# electronic_piano.net
KiCad netlist of a schematic drawn in EAGLE
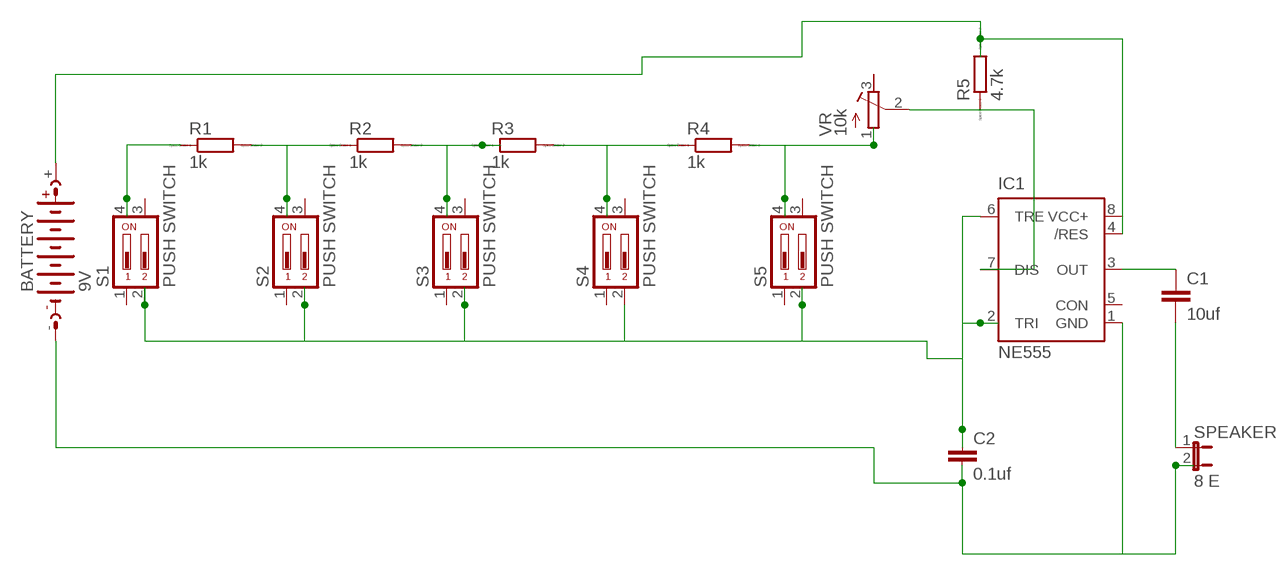
[diagram p0: schematic, sheet 1]

(export (version "E")
  (design (tool "Eeschema 10.0.6"))
  (components
    (comp (ref "BATTERY")
      (value "9V")
      (footprint "eagle-import:AB9V")
      (libsource (lib "eagle-import") (part "AB9V"))
    )
    (comp (ref "C1")
      (value "10uf")
      (footprint "eagle-import:C5B7.2")
      (libsource (lib "eagle-import") (part "C5/7.2"))
    )
    (comp (ref "C2")
      (value "0.1uf")
      (footprint "eagle-import:C2.5-2")
      (libsource (lib "eagle-import") (part "C2.5/2"))
    )
    (comp (ref "IC1")
      (value "NE555")
      (footprint "eagle-import:DIL-08")
      (fields (field (name "MF") "Arrow Electronics") (field (name "MPN") "NE555N"))
      (libsource (lib "eagle-import") (part "NE555"))
    )
    (comp (ref "R1")
      (value "1k")
      (footprint "eagle-import:0204_7")
      (libsource (lib "eagle-import") (part "R0204/7"))
    )
    (comp (ref "R2")
      (value "1k")
      (footprint "eagle-import:0204_7")
      (libsource (lib "eagle-import") (part "R0204/7"))
    )
    (comp (ref "R3")
      (value "1k")
      (footprint "eagle-import:0204_7")
      (libsource (lib "eagle-import") (part "R0204/7"))
    )
    (comp (ref "R4")
      (value "1k")
      (footprint "eagle-import:0204_7")
      (libsource (lib "eagle-import") (part "R0204/7"))
    )
    (comp (ref "R5")
      (value "4.7k")
      (footprint "eagle-import:0204_7")
      (libsource (lib "eagle-import") (part "R0204/7"))
    )
    (comp (ref "S1")
      (value "PUSH SWITCH")
      (footprint "eagle-import:DS-02")
      (libsource (lib "eagle-import") (part "DS02"))
    )
    (comp (ref "S2")
      (value "PUSH SWITCH")
      (footprint "eagle-import:DS-02")
      (libsource (lib "eagle-import") (part "DS02"))
    )
    (comp (ref "S3")
      (value "PUSH SWITCH")
      (footprint "eagle-import:DS-02")
      (libsource (lib "eagle-import") (part "DS02"))
    )
    (comp (ref "S4")
      (value "PUSH SWITCH")
      (footprint "eagle-import:DS-02")
      (libsource (lib "eagle-import") (part "DS02"))
    )
    (comp (ref "S5")
      (value "PUSH SWITCH")
      (footprint "eagle-import:DS-02")
      (libsource (lib "eagle-import") (part "DS02"))
    )
    (comp (ref "SPEAKER")
      (value "8 E")
      (footprint "eagle-import:JP1")
      (libsource (lib "eagle-import") (part "JP1E"))
    )
    (comp (ref "VR")
      (value "10k")
      (footprint "eagle-import:RTRIM64P")
      (libsource (lib "eagle-import") (part "R-TRIMM64P"))
    )
  )
  (nets
    (net (code "1") (name "Net-(C1-Pad2)") (class "Default")
      (node (ref "C1") (pin "2") (pinfunction "2_2") (pintype "passive"))
      (node (ref "SPEAKER") (pin "1") (pinfunction "1_1") (pintype "passive"))
    )
    (net (code "2") (name "Net-(IC1-DIS)") (class "Default")
      (node (ref "IC1") (pin "7") (pinfunction "DIS_7") (pintype "input"))
      (node (ref "R5") (pin "1") (pinfunction "1_1") (pintype "passive"))
      (node (ref "VR") (pin "2") (pinfunction "S_2") (pintype "passive"))
    )
    (net (code "3") (name "Net-(IC1-GND)") (class "Default")
      (node (ref "BATTERY") (pin "-") (pinfunction "-_-") (pintype "passive"))
      (node (ref "C2") (pin "2") (pinfunction "2_2") (pintype "passive"))
      (node (ref "IC1") (pin "1") (pinfunction "GND_1") (pintype "power_in"))
      (node (ref "SPEAKER") (pin "2") (pinfunction "2_2") (pintype "passive"))
    )
    (net (code "4") (name "Net-(IC1-OUT)") (class "Default")
      (node (ref "C1") (pin "1") (pinfunction "1_1") (pintype "passive"))
      (node (ref "IC1") (pin "3") (pinfunction "OUT_3") (pintype "output"))
    )
    (net (code "5") (name "Net-(IC1-TRE)") (class "Default")
      (node (ref "C2") (pin "1") (pinfunction "1_1") (pintype "passive"))
      (node (ref "IC1") (pin "2") (pinfunction "TRI_2") (pintype "input"))
      (node (ref "IC1") (pin "6") (pinfunction "TRE_6") (pintype "input"))
      (node (ref "S1") (pin "2") (pinfunction "2_2") (pintype "passive"))
      (node (ref "S2") (pin "2") (pinfunction "2_2") (pintype "passive"))
      (node (ref "S3") (pin "2") (pinfunction "2_2") (pintype "passive"))
      (node (ref "S4") (pin "2") (pinfunction "2_2") (pintype "passive"))
      (node (ref "S5") (pin "2") (pinfunction "2_2") (pintype "passive"))
    )
    (net (code "6") (name "Net-(IC1-VCC+)") (class "Default")
      (node (ref "BATTERY") (pin "+") (pinfunction "+_+") (pintype "passive"))
      (node (ref "IC1") (pin "4") (pinfunction "/RES_4") (pintype "input"))
      (node (ref "IC1") (pin "8") (pinfunction "VCC+_8") (pintype "power_in"))
      (node (ref "R5") (pin "2") (pinfunction "2_2") (pintype "passive"))
    )
    (net (code "7") (name "Net-(R1-Pad1)") (class "Default")
      (node (ref "R1") (pin "1") (pinfunction "1_1") (pintype "passive"))
      (node (ref "S1") (pin "4") (pinfunction "4_4") (pintype "passive"))
    )
    (net (code "8") (name "Net-(R1-Pad2)") (class "Default")
      (node (ref "R1") (pin "2") (pinfunction "2_2") (pintype "passive"))
      (node (ref "R2") (pin "1") (pinfunction "1_1") (pintype "passive"))
      (node (ref "S2") (pin "4") (pinfunction "4_4") (pintype "passive"))
    )
    (net (code "9") (name "Net-(R2-Pad2)") (class "Default")
      (node (ref "R2") (pin "2") (pinfunction "2_2") (pintype "passive"))
      (node (ref "R3") (pin "1") (pinfunction "1_1") (pintype "passive"))
      (node (ref "S3") (pin "4") (pinfunction "4_4") (pintype "passive"))
    )
    (net (code "10") (name "Net-(R3-Pad2)") (class "Default")
      (node (ref "R3") (pin "2") (pinfunction "2_2") (pintype "passive"))
      (node (ref "R4") (pin "1") (pinfunction "1_1") (pintype "passive"))
      (node (ref "S4") (pin "4") (pinfunction "4_4") (pintype "passive"))
    )
    (net (code "11") (name "Net-(VR-E)") (class "Default")
      (node (ref "R4") (pin "2") (pinfunction "2_2") (pintype "passive"))
      (node (ref "S5") (pin "4") (pinfunction "4_4") (pintype "passive"))
      (node (ref "VR") (pin "1") (pinfunction "E_1") (pintype "passive"))
    )
    (net (code "12") (name "unconnected-(IC1-CON-Pad5)") (class "Default")
      (node (ref "IC1") (pin "5") (pinfunction "CON_5") (pintype "input"))
    )
    (net (code "13") (name "unconnected-(S1-Pad1)") (class "Default")
      (node (ref "S1") (pin "1") (pinfunction "1_1") (pintype "passive"))
    )
    (net (code "14") (name "unconnected-(S1-Pad3)") (class "Default")
      (node (ref "S1") (pin "3") (pinfunction "3_3") (pintype "passive"))
    )
    (net (code "15") (name "unconnected-(S2-Pad1)") (class "Default")
      (node (ref "S2") (pin "1") (pinfunction "1_1") (pintype "passive"))
    )
    (net (code "16") (name "unconnected-(S2-Pad3)") (class "Default")
      (node (ref "S2") (pin "3") (pinfunction "3_3") (pintype "passive"))
    )
    (net (code "17") (name "unconnected-(S3-Pad1)") (class "Default")
      (node (ref "S3") (pin "1") (pinfunction "1_1") (pintype "passive"))
    )
    (net (code "18") (name "unconnected-(S3-Pad3)") (class "Default")
      (node (ref "S3") (pin "3") (pinfunction "3_3") (pintype "passive"))
    )
    (net (code "19") (name "unconnected-(S4-Pad1)") (class "Default")
      (node (ref "S4") (pin "1") (pinfunction "1_1") (pintype "passive"))
    )
    (net (code "20") (name "unconnected-(S4-Pad3)") (class "Default")
      (node (ref "S4") (pin "3") (pinfunction "3_3") (pintype "passive"))
    )
    (net (code "21") (name "unconnected-(S5-Pad1)") (class "Default")
      (node (ref "S5") (pin "1") (pinfunction "1_1") (pintype "passive"))
    )
    (net (code "22") (name "unconnected-(S5-Pad3)") (class "Default")
      (node (ref "S5") (pin "3") (pinfunction "3_3") (pintype "passive"))
    )
    (net (code "23") (name "unconnected-(VR-A-Pad3)") (class "Default")
      (node (ref "VR") (pin "3") (pinfunction "A_3") (pintype "passive"))
    )
  )
)
